# ADS5553.net
KiCad netlist of a schematic drawn in Altium Designer
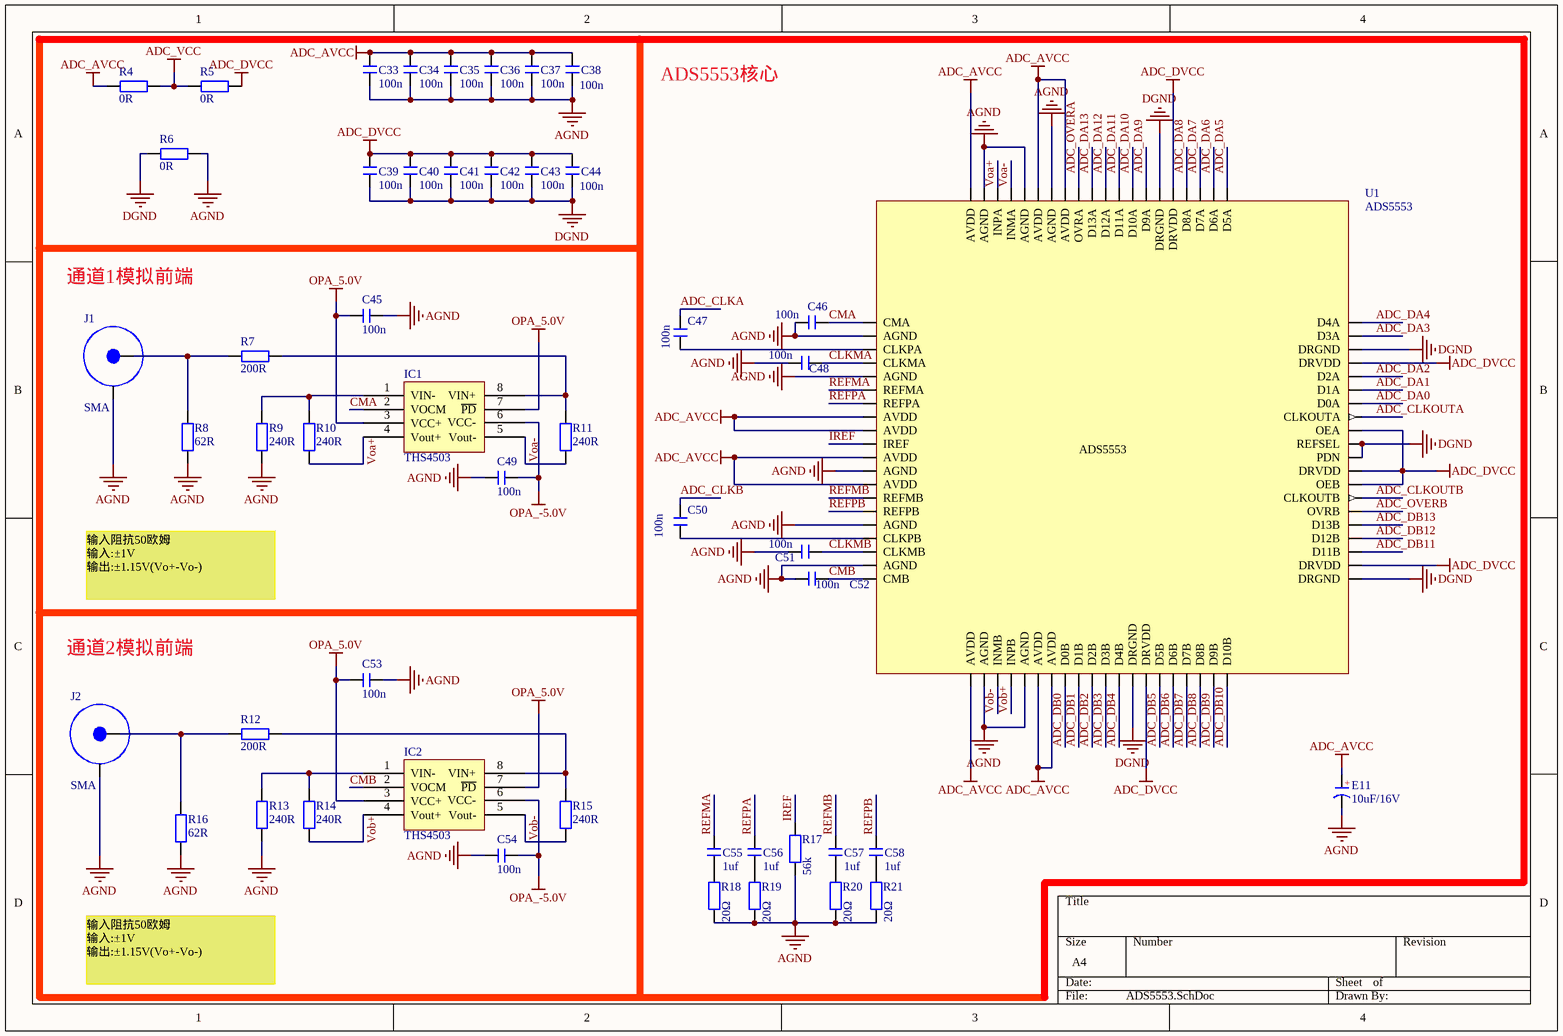
[diagram p0: ADS5553.SchDoc]

(export (version "E")
  (design (tool "Eeschema 10.0.6"))
  (components
    (comp (ref "C33")
      (value "100n")
      (footprint "C 0805_M")
      (description "无极性贴片电容")
      (fields (field (name "版权归属") "源创客"))
      (libsource (lib "3.1   - 电阻-电容-电感") (part "C"))
    )
    (comp (ref "C34")
      (value "100n")
      (footprint "C 0805_M")
      (description "无极性贴片电容")
      (fields (field (name "版权归属") "源创客"))
      (libsource (lib "3.1   - 电阻-电容-电感") (part "C"))
    )
    (comp (ref "C35")
      (value "100n")
      (footprint "C 0805_M")
      (description "无极性贴片电容")
      (fields (field (name "版权归属") "源创客"))
      (libsource (lib "3.1   - 电阻-电容-电感") (part "C"))
    )
    (comp (ref "C36")
      (value "100n")
      (footprint "C 0805_M")
      (description "无极性贴片电容")
      (fields (field (name "版权归属") "源创客"))
      (libsource (lib "3.1   - 电阻-电容-电感") (part "C"))
    )
    (comp (ref "C37")
      (value "100n")
      (footprint "C 0805_M")
      (description "无极性贴片电容")
      (fields (field (name "版权归属") "源创客"))
      (libsource (lib "3.1   - 电阻-电容-电感") (part "C"))
    )
    (comp (ref "C38")
      (value "100n")
      (footprint "C 0805_M")
      (description "无极性贴片电容")
      (fields (field (name "版权归属") "源创客"))
      (libsource (lib "3.1   - 电阻-电容-电感") (part "C"))
    )
    (comp (ref "C39")
      (value "100n")
      (footprint "C 0805_M")
      (description "无极性贴片电容")
      (fields (field (name "版权归属") "源创客"))
      (libsource (lib "3.1   - 电阻-电容-电感") (part "C"))
    )
    (comp (ref "C40")
      (value "100n")
      (footprint "C 0805_M")
      (description "无极性贴片电容")
      (fields (field (name "版权归属") "源创客"))
      (libsource (lib "3.1   - 电阻-电容-电感") (part "C"))
    )
    (comp (ref "C41")
      (value "100n")
      (footprint "C 0805_M")
      (description "无极性贴片电容")
      (fields (field (name "版权归属") "源创客"))
      (libsource (lib "3.1   - 电阻-电容-电感") (part "C"))
    )
    (comp (ref "C42")
      (value "100n")
      (footprint "C 0805_M")
      (description "无极性贴片电容")
      (fields (field (name "版权归属") "源创客"))
      (libsource (lib "3.1   - 电阻-电容-电感") (part "C"))
    )
    (comp (ref "C43")
      (value "100n")
      (footprint "C 0805_M")
      (description "无极性贴片电容")
      (fields (field (name "版权归属") "源创客"))
      (libsource (lib "3.1   - 电阻-电容-电感") (part "C"))
    )
    (comp (ref "C44")
      (value "100n")
      (footprint "C 0805_M")
      (description "无极性贴片电容")
      (fields (field (name "版权归属") "源创客"))
      (libsource (lib "3.1   - 电阻-电容-电感") (part "C"))
    )
    (comp (ref "C45")
      (value "100n")
      (footprint "C 0805_M")
      (description "无极性贴片电容")
      (fields (field (name "版权归属") "源创客"))
      (libsource (lib "3.1   - 电阻-电容-电感") (part "C"))
    )
    (comp (ref "C46")
      (value "100n")
      (footprint "C 0805_M")
      (description "无极性贴片电容")
      (fields (field (name "版权归属") "源创客"))
      (libsource (lib "3.1   - 电阻-电容-电感") (part "C"))
    )
    (comp (ref "C47")
      (value "100n")
      (footprint "C 0805_M")
      (description "无极性贴片电容")
      (fields (field (name "版权归属") "源创客"))
      (libsource (lib "3.1   - 电阻-电容-电感") (part "C"))
    )
    (comp (ref "C48")
      (value "100n")
      (footprint "C 0805_M")
      (description "无极性贴片电容")
      (fields (field (name "版权归属") "源创客"))
      (libsource (lib "3.1   - 电阻-电容-电感") (part "C"))
    )
    (comp (ref "C49")
      (value "100n")
      (footprint "C 0805_M")
      (description "无极性贴片电容")
      (fields (field (name "版权归属") "源创客"))
      (libsource (lib "3.1   - 电阻-电容-电感") (part "C"))
    )
    (comp (ref "C50")
      (value "100n")
      (footprint "C 0805_M")
      (description "无极性贴片电容")
      (fields (field (name "版权归属") "源创客"))
      (libsource (lib "3.1   - 电阻-电容-电感") (part "C"))
    )
    (comp (ref "C51")
      (value "100n")
      (footprint "C 0805_M")
      (description "无极性贴片电容")
      (fields (field (name "版权归属") "源创客"))
      (libsource (lib "3.1   - 电阻-电容-电感") (part "C"))
    )
    (comp (ref "C52")
      (value "100n")
      (footprint "C 0805_M")
      (description "无极性贴片电容")
      (fields (field (name "版权归属") "源创客"))
      (libsource (lib "3.1   - 电阻-电容-电感") (part "C"))
    )
    (comp (ref "C53")
      (value "100n")
      (footprint "C 0805_M")
      (description "无极性贴片电容")
      (fields (field (name "版权归属") "源创客"))
      (libsource (lib "3.1   - 电阻-电容-电感") (part "C"))
    )
    (comp (ref "C54")
      (value "100n")
      (footprint "C 0805_M")
      (description "无极性贴片电容")
      (fields (field (name "版权归属") "源创客"))
      (libsource (lib "3.1   - 电阻-电容-电感") (part "C"))
    )
    (comp (ref "C55")
      (value "1uf")
      (footprint "C 0805_M")
      (description "无极性贴片电容")
      (fields (field (name "版权归属") "源创客"))
      (libsource (lib "3.1   - 电阻-电容-电感") (part "C"))
    )
    (comp (ref "C56")
      (value "1uf")
      (footprint "C 0805_M")
      (description "无极性贴片电容")
      (fields (field (name "版权归属") "源创客"))
      (libsource (lib "3.1   - 电阻-电容-电感") (part "C"))
    )
    (comp (ref "C57")
      (value "1uf")
      (footprint "C 0805_M")
      (description "无极性贴片电容")
      (fields (field (name "版权归属") "源创客"))
      (libsource (lib "3.1   - 电阻-电容-电感") (part "C"))
    )
    (comp (ref "C58")
      (value "1uf")
      (footprint "C 0805_M")
      (description "无极性贴片电容")
      (fields (field (name "版权归属") "源创客"))
      (libsource (lib "3.1   - 电阻-电容-电感") (part "C"))
    )
    (comp (ref "E11")
      (value "10uF/16V")
      (footprint "C 1210_M")
      (description "直插电解电容")
      (fields (field (name "版权归属") "源创客"))
      (libsource (lib "3.1   - 电阻-电容-电感") (part "C-CAP"))
    )
    (comp (ref "IC1")
      (value "THS4503")
      (footprint "SOP8_M")
      (description "外置EEPROM")
      (fields (field (name "版权归属") "源创客"))
      (libsource (lib "1.1   - IC芯片") (part "24Cxx"))
    )
    (comp (ref "IC2")
      (value "THS4503")
      (footprint "SOP8_M")
      (description "外置EEPROM")
      (fields (field (name "版权归属") "源创客"))
      (libsource (lib "1.1   - IC芯片") (part "24Cxx"))
    )
    (comp (ref "J1") (value "SMA") (footprint "SMA_FR") (libsource (lib "RF") (part "SMA")))
    (comp (ref "J2") (value "SMA") (footprint "SMA_FR") (libsource (lib "RF") (part "SMA")))
    (comp (ref "R4")
      (value "0R")
      (footprint "R 0805_M")
      (description "贴片电阻")
      (fields (field (name "版权归属") "源创客"))
      (libsource (lib "3.1   - 电阻-电容-电感") (part "R"))
    )
    (comp (ref "R5")
      (value "0R")
      (footprint "R 0805_M")
      (description "贴片电阻")
      (fields (field (name "版权归属") "源创客"))
      (libsource (lib "3.1   - 电阻-电容-电感") (part "R"))
    )
    (comp (ref "R6")
      (value "0R")
      (footprint "R 1206_M")
      (description "贴片电阻")
      (fields (field (name "版权归属") "源创客"))
      (libsource (lib "3.1   - 电阻-电容-电感") (part "R"))
    )
    (comp (ref "R7")
      (value "200R")
      (footprint "R 0805_M")
      (description "贴片电阻")
      (fields (field (name "版权归属") "源创客"))
      (libsource (lib "3.1   - 电阻-电容-电感") (part "R"))
    )
    (comp (ref "R8")
      (value "62R")
      (footprint "R 0805_M")
      (description "贴片电阻")
      (fields (field (name "版权归属") "源创客"))
      (libsource (lib "3.1   - 电阻-电容-电感") (part "R"))
    )
    (comp (ref "R9")
      (value "240R")
      (footprint "R 0805_M")
      (description "贴片电阻")
      (fields (field (name "版权归属") "源创客"))
      (libsource (lib "3.1   - 电阻-电容-电感") (part "R"))
    )
    (comp (ref "R10")
      (value "240R")
      (footprint "R 0805_M")
      (description "贴片电阻")
      (fields (field (name "版权归属") "源创客"))
      (libsource (lib "3.1   - 电阻-电容-电感") (part "R"))
    )
    (comp (ref "R11")
      (value "240R")
      (footprint "R 0805_M")
      (description "贴片电阻")
      (fields (field (name "版权归属") "源创客"))
      (libsource (lib "3.1   - 电阻-电容-电感") (part "R"))
    )
    (comp (ref "R12")
      (value "200R")
      (footprint "R 0805_M")
      (description "贴片电阻")
      (fields (field (name "版权归属") "源创客"))
      (libsource (lib "3.1   - 电阻-电容-电感") (part "R"))
    )
    (comp (ref "R13")
      (value "240R")
      (footprint "R 0805_M")
      (description "贴片电阻")
      (fields (field (name "版权归属") "源创客"))
      (libsource (lib "3.1   - 电阻-电容-电感") (part "R"))
    )
    (comp (ref "R14")
      (value "240R")
      (footprint "R 0805_M")
      (description "贴片电阻")
      (fields (field (name "版权归属") "源创客"))
      (libsource (lib "3.1   - 电阻-电容-电感") (part "R"))
    )
    (comp (ref "R15")
      (value "240R")
      (footprint "R 0805_M")
      (description "贴片电阻")
      (fields (field (name "版权归属") "源创客"))
      (libsource (lib "3.1   - 电阻-电容-电感") (part "R"))
    )
    (comp (ref "R16")
      (value "62R")
      (footprint "R 0805_M")
      (description "贴片电阻")
      (fields (field (name "版权归属") "源创客"))
      (libsource (lib "3.1   - 电阻-电容-电感") (part "R"))
    )
    (comp (ref "R17")
      (value "56k")
      (footprint "R 0805_M")
      (description "贴片电阻")
      (fields (field (name "版权归属") "源创客"))
      (libsource (lib "3.1   - 电阻-电容-电感") (part "R"))
    )
    (comp (ref "R18")
      (value "20Ω")
      (footprint "R 0805_M")
      (description "贴片电阻")
      (fields (field (name "版权归属") "源创客"))
      (libsource (lib "3.1   - 电阻-电容-电感") (part "R"))
    )
    (comp (ref "R19")
      (value "20Ω")
      (footprint "R 0805_M")
      (description "贴片电阻")
      (fields (field (name "版权归属") "源创客"))
      (libsource (lib "3.1   - 电阻-电容-电感") (part "R"))
    )
    (comp (ref "R20")
      (value "20Ω")
      (footprint "R 0805_M")
      (description "贴片电阻")
      (fields (field (name "版权归属") "源创客"))
      (libsource (lib "3.1   - 电阻-电容-电感") (part "R"))
    )
    (comp (ref "R21")
      (value "20Ω")
      (footprint "R 0805_M")
      (description "贴片电阻")
      (fields (field (name "版权归属") "源创客"))
      (libsource (lib "3.1   - 电阻-电容-电感") (part "R"))
    )
    (comp (ref "U1")
      (value "ADS5553")
      (footprint "LQFP80 12x12_M")
      (libsource (lib "ADS5553") (part "ADS5553"))
    )
  )
  (nets
    (net (code "1") (name "/ADC_CLKA") (class "Default")
      (node (ref "C47") (pin "2") (pinfunction "2_2") (pintype "passive"))
    )
    (net (code "2") (name "/ADC_CLKB") (class "Default")
      (node (ref "C50") (pin "2") (pinfunction "2_2") (pintype "passive"))
    )
    (net (code "3") (name "/ADC_CLKOUTA") (class "Default")
      (node (ref "U1") (pin "53") (pinfunction "CLKOUTA_53") (pintype "output"))
    )
    (net (code "4") (name "/ADC_CLKOUTB") (class "Default")
      (node (ref "U1") (pin "47") (pinfunction "CLKOUTB_47") (pintype "output"))
    )
    (net (code "5") (name "/ADC_DA0") (class "Default")
      (node (ref "U1") (pin "54") (pinfunction "D0A_54") (pintype "passive"))
    )
    (net (code "6") (name "/ADC_DA1") (class "Default")
      (node (ref "U1") (pin "55") (pinfunction "D1A_55") (pintype "passive"))
    )
    (net (code "7") (name "/ADC_DA2") (class "Default")
      (node (ref "U1") (pin "56") (pinfunction "D2A_56") (pintype "passive"))
    )
    (net (code "8") (name "/ADC_DA3") (class "Default")
      (node (ref "U1") (pin "59") (pinfunction "D3A_59") (pintype "passive"))
    )
    (net (code "9") (name "/ADC_DA4") (class "Default")
      (node (ref "U1") (pin "60") (pinfunction "D4A_60") (pintype "passive"))
    )
    (net (code "10") (name "/ADC_DA5") (class "Default")
      (node (ref "U1") (pin "61") (pinfunction "D5A_61") (pintype "passive"))
    )
    (net (code "11") (name "/ADC_DA6") (class "Default")
      (node (ref "U1") (pin "62") (pinfunction "D6A_62") (pintype "passive"))
    )
    (net (code "12") (name "/ADC_DA7") (class "Default")
      (node (ref "U1") (pin "63") (pinfunction "D7A_63") (pintype "passive"))
    )
    (net (code "13") (name "/ADC_DA8") (class "Default")
      (node (ref "U1") (pin "64") (pinfunction "D8A_64") (pintype "passive"))
    )
    (net (code "14") (name "/ADC_DA9") (class "Default")
      (node (ref "U1") (pin "67") (pinfunction "D9A_67") (pintype "passive"))
    )
    (net (code "15") (name "/ADC_DA10") (class "Default")
      (node (ref "U1") (pin "68") (pinfunction "D10A_68") (pintype "passive"))
    )
    (net (code "16") (name "/ADC_DA11") (class "Default")
      (node (ref "U1") (pin "69") (pinfunction "D11A_69") (pintype "passive"))
    )
    (net (code "17") (name "/ADC_DA12") (class "Default")
      (node (ref "U1") (pin "70") (pinfunction "D12A_70") (pintype "passive"))
    )
    (net (code "18") (name "/ADC_DA13") (class "Default")
      (node (ref "U1") (pin "71") (pinfunction "D13A_71") (pintype "passive"))
    )
    (net (code "19") (name "/ADC_DB0") (class "Default")
      (node (ref "U1") (pin "28") (pinfunction "D0B_28") (pintype "passive"))
    )
    (net (code "20") (name "/ADC_DB1") (class "Default")
      (node (ref "U1") (pin "29") (pinfunction "D1B_29") (pintype "passive"))
    )
    (net (code "21") (name "/ADC_DB2") (class "Default")
      (node (ref "U1") (pin "30") (pinfunction "D2B_30") (pintype "passive"))
    )
    (net (code "22") (name "/ADC_DB3") (class "Default")
      (node (ref "U1") (pin "31") (pinfunction "D3B_31") (pintype "passive"))
    )
    (net (code "23") (name "/ADC_DB4") (class "Default")
      (node (ref "U1") (pin "32") (pinfunction "D4B_32") (pintype "passive"))
    )
    (net (code "24") (name "/ADC_DB5") (class "Default")
      (node (ref "U1") (pin "35") (pinfunction "D5B_35") (pintype "passive"))
    )
    (net (code "25") (name "/ADC_DB6") (class "Default")
      (node (ref "U1") (pin "36") (pinfunction "D6B_36") (pintype "passive"))
    )
    (net (code "26") (name "/ADC_DB7") (class "Default")
      (node (ref "U1") (pin "37") (pinfunction "D7B_37") (pintype "passive"))
    )
    (net (code "27") (name "/ADC_DB8") (class "Default")
      (node (ref "U1") (pin "38") (pinfunction "D8B_38") (pintype "passive"))
    )
    (net (code "28") (name "/ADC_DB9") (class "Default")
      (node (ref "U1") (pin "39") (pinfunction "D9B_39") (pintype "passive"))
    )
    (net (code "29") (name "/ADC_DB10") (class "Default")
      (node (ref "U1") (pin "40") (pinfunction "D10B_40") (pintype "passive"))
    )
    (net (code "30") (name "/ADC_DB11") (class "Default")
      (node (ref "U1") (pin "43") (pinfunction "D11B_43") (pintype "passive"))
    )
    (net (code "31") (name "/ADC_DB12") (class "Default")
      (node (ref "U1") (pin "44") (pinfunction "D12B_44") (pintype "passive"))
    )
    (net (code "32") (name "/ADC_DB13") (class "Default")
      (node (ref "U1") (pin "45") (pinfunction "D13B_45") (pintype "passive"))
    )
    (net (code "33") (name "/ADC_OVERA") (class "Default")
      (node (ref "U1") (pin "72") (pinfunction "OVRA_72") (pintype "passive"))
    )
    (net (code "34") (name "/ADC_OVERB") (class "Default")
      (node (ref "U1") (pin "46") (pinfunction "OVRB_46") (pintype "passive"))
    )
    (net (code "35") (name "/CLKMA") (class "Default")
      (node (ref "C48") (pin "2") (pinfunction "2_2") (pintype "passive"))
      (node (ref "U1") (pin "4") (pinfunction "CLKMA_4") (pintype "passive"))
    )
    (net (code "36") (name "/CLKMB") (class "Default")
      (node (ref "C51") (pin "2") (pinfunction "2_2") (pintype "passive"))
      (node (ref "U1") (pin "18") (pinfunction "CLKMB_18") (pintype "passive"))
    )
    (net (code "37") (name "/CMA") (class "Default")
      (node (ref "C46") (pin "2") (pinfunction "2_2") (pintype "passive"))
      (node (ref "IC1") (pin "2") (pinfunction "VOCM_2") (pintype "passive"))
      (node (ref "U1") (pin "1") (pinfunction "CMA_1") (pintype "passive"))
    )
    (net (code "38") (name "/CMB") (class "Default")
      (node (ref "C52") (pin "2") (pinfunction "2_2") (pintype "passive"))
      (node (ref "IC2") (pin "2") (pinfunction "VOCM_2") (pintype "passive"))
      (node (ref "U1") (pin "20") (pinfunction "CMB_20") (pintype "passive"))
    )
    (net (code "39") (name "/IREF") (class "Default")
      (node (ref "R17") (pin "2") (pinfunction "2_2") (pintype "passive"))
      (node (ref "U1") (pin "10") (pinfunction "IREF_10") (pintype "passive"))
    )
    (net (code "40") (name "/REFMA") (class "Default")
      (node (ref "C55") (pin "2") (pinfunction "2_2") (pintype "passive"))
      (node (ref "U1") (pin "6") (pinfunction "REFMA_6") (pintype "passive"))
    )
    (net (code "41") (name "/REFMB") (class "Default")
      (node (ref "C57") (pin "2") (pinfunction "2_2") (pintype "passive"))
      (node (ref "U1") (pin "14") (pinfunction "REFMB_14") (pintype "passive"))
    )
    (net (code "42") (name "/REFPA") (class "Default")
      (node (ref "C56") (pin "2") (pinfunction "2_2") (pintype "passive"))
      (node (ref "U1") (pin "7") (pinfunction "REFPA_7") (pintype "passive"))
    )
    (net (code "43") (name "/REFPB") (class "Default")
      (node (ref "C58") (pin "2") (pinfunction "2_2") (pintype "passive"))
      (node (ref "U1") (pin "15") (pinfunction "REFPB_15") (pintype "passive"))
    )
    (net (code "44") (name "/Voa+") (class "Default")
      (node (ref "IC1") (pin "4") (pinfunction "Vout+_4") (pintype "passive"))
      (node (ref "R10") (pin "1") (pinfunction "1_1") (pintype "passive"))
      (node (ref "U1") (pin "78") (pinfunction "INPA_78") (pintype "passive"))
    )
    (net (code "45") (name "/Voa-") (class "Default")
      (node (ref "IC1") (pin "5") (pinfunction "Vout-_5") (pintype "passive"))
      (node (ref "R11") (pin "1") (pinfunction "1_1") (pintype "passive"))
      (node (ref "U1") (pin "77") (pinfunction "INMA_77") (pintype "passive"))
    )
    (net (code "46") (name "/Vob+") (class "Default")
      (node (ref "IC2") (pin "4") (pinfunction "Vout+_4") (pintype "passive"))
      (node (ref "R14") (pin "1") (pinfunction "1_1") (pintype "passive"))
      (node (ref "U1") (pin "24") (pinfunction "INPB_24") (pintype "passive"))
    )
    (net (code "47") (name "/Vob-") (class "Default")
      (node (ref "IC2") (pin "5") (pinfunction "Vout-_5") (pintype "passive"))
      (node (ref "R15") (pin "1") (pinfunction "1_1") (pintype "passive"))
      (node (ref "U1") (pin "23") (pinfunction "INMB_23") (pintype "passive"))
    )
    (net (code "48") (name "ADC_AVCC") (class "Default")
      (node (ref "C33") (pin "2") (pinfunction "2_2") (pintype "passive"))
      (node (ref "C34") (pin "2") (pinfunction "2_2") (pintype "passive"))
      (node (ref "C35") (pin "2") (pinfunction "2_2") (pintype "passive"))
      (node (ref "C36") (pin "2") (pinfunction "2_2") (pintype "passive"))
      (node (ref "C37") (pin "2") (pinfunction "2_2") (pintype "passive"))
      (node (ref "C38") (pin "2") (pinfunction "2_2") (pintype "passive"))
      (node (ref "E11") (pin "1") (pinfunction "A_1") (pintype "passive"))
      (node (ref "R4") (pin "2") (pinfunction "2_2") (pintype "passive"))
      (node (ref "U1") (pin "11") (pinfunction "AVDD_11") (pintype "passive"))
      (node (ref "U1") (pin "13") (pinfunction "AVDD_13") (pintype "passive"))
      (node (ref "U1") (pin "21") (pinfunction "AVDD_21") (pintype "passive"))
      (node (ref "U1") (pin "26") (pinfunction "AVDD_26") (pintype "passive"))
      (node (ref "U1") (pin "27") (pinfunction "AVDD_27") (pintype "passive"))
      (node (ref "U1") (pin "73") (pinfunction "AVDD_73") (pintype "passive"))
      (node (ref "U1") (pin "75") (pinfunction "AVDD_75") (pintype "passive"))
      (node (ref "U1") (pin "8") (pinfunction "AVDD_8") (pintype "passive"))
      (node (ref "U1") (pin "80") (pinfunction "AVDD_80") (pintype "passive"))
      (node (ref "U1") (pin "9") (pinfunction "AVDD_9") (pintype "passive"))
    )
    (net (code "49") (name "ADC_DVCC") (class "Default")
      (node (ref "C39") (pin "2") (pinfunction "2_2") (pintype "passive"))
      (node (ref "C40") (pin "2") (pinfunction "2_2") (pintype "passive"))
      (node (ref "C41") (pin "2") (pinfunction "2_2") (pintype "passive"))
      (node (ref "C42") (pin "2") (pinfunction "2_2") (pintype "passive"))
      (node (ref "C43") (pin "2") (pinfunction "2_2") (pintype "passive"))
      (node (ref "C44") (pin "2") (pinfunction "2_2") (pintype "passive"))
      (node (ref "R5") (pin "1") (pinfunction "1_1") (pintype "passive"))
      (node (ref "U1") (pin "34") (pinfunction "DRVDD_34") (pintype "passive"))
      (node (ref "U1") (pin "42") (pinfunction "DRVDD_42") (pintype "passive"))
      (node (ref "U1") (pin "48") (pinfunction "OEB_48") (pintype "passive"))
      (node (ref "U1") (pin "49") (pinfunction "DRVDD_49") (pintype "passive"))
      (node (ref "U1") (pin "52") (pinfunction "OEA_52") (pintype "passive"))
      (node (ref "U1") (pin "57") (pinfunction "DRVDD_57") (pintype "passive"))
      (node (ref "U1") (pin "65") (pinfunction "DRVDD_65") (pintype "passive"))
    )
    (net (code "50") (name "ADC_VCC") (class "Default")
      (node (ref "R4") (pin "1") (pinfunction "1_1") (pintype "passive"))
      (node (ref "R5") (pin "2") (pinfunction "2_2") (pintype "passive"))
    )
    (net (code "51") (name "AGND") (class "Default")
      (node (ref "C33") (pin "1") (pinfunction "1_1") (pintype "passive"))
      (node (ref "C34") (pin "1") (pinfunction "1_1") (pintype "passive"))
      (node (ref "C35") (pin "1") (pinfunction "1_1") (pintype "passive"))
      (node (ref "C36") (pin "1") (pinfunction "1_1") (pintype "passive"))
      (node (ref "C37") (pin "1") (pinfunction "1_1") (pintype "passive"))
      (node (ref "C38") (pin "1") (pinfunction "1_1") (pintype "passive"))
      (node (ref "C45") (pin "2") (pinfunction "2_2") (pintype "passive"))
      (node (ref "C46") (pin "1") (pinfunction "1_1") (pintype "passive"))
      (node (ref "C48") (pin "1") (pinfunction "1_1") (pintype "passive"))
      (node (ref "C49") (pin "1") (pinfunction "1_1") (pintype "passive"))
      (node (ref "C51") (pin "1") (pinfunction "1_1") (pintype "passive"))
      (node (ref "C52") (pin "1") (pinfunction "1_1") (pintype "passive"))
      (node (ref "C53") (pin "2") (pinfunction "2_2") (pintype "passive"))
      (node (ref "C54") (pin "1") (pinfunction "1_1") (pintype "passive"))
      (node (ref "E11") (pin "2") (pinfunction "K_2") (pintype "passive"))
      (node (ref "J1") (pin "2") (pinfunction "2_2") (pintype "passive"))
      (node (ref "J2") (pin "2") (pinfunction "2_2") (pintype "passive"))
      (node (ref "R13") (pin "1") (pinfunction "1_1") (pintype "passive"))
      (node (ref "R16") (pin "1") (pinfunction "1_1") (pintype "passive"))
      (node (ref "R17") (pin "1") (pinfunction "1_1") (pintype "passive"))
      (node (ref "R18") (pin "1") (pinfunction "1_1") (pintype "passive"))
      (node (ref "R19") (pin "1") (pinfunction "1_1") (pintype "passive"))
      (node (ref "R20") (pin "1") (pinfunction "1_1") (pintype "passive"))
      (node (ref "R21") (pin "1") (pinfunction "1_1") (pintype "passive"))
      (node (ref "R6") (pin "1") (pinfunction "1_1") (pintype "passive"))
      (node (ref "R8") (pin "2") (pinfunction "2_2") (pintype "passive"))
      (node (ref "R9") (pin "1") (pinfunction "1_1") (pintype "passive"))
      (node (ref "U1") (pin "12") (pinfunction "AGND_12") (pintype "passive"))
      (node (ref "U1") (pin "16") (pinfunction "AGND_16") (pintype "passive"))
      (node (ref "U1") (pin "19") (pinfunction "AGND_19") (pintype "passive"))
      (node (ref "U1") (pin "2") (pinfunction "AGND_2") (pintype "passive"))
      (node (ref "U1") (pin "22") (pinfunction "AGND_22") (pintype "passive"))
      (node (ref "U1") (pin "25") (pinfunction "AGND_25") (pintype "passive"))
      (node (ref "U1") (pin "5") (pinfunction "AGND_5") (pintype "passive"))
      (node (ref "U1") (pin "74") (pinfunction "AGND_74") (pintype "passive"))
      (node (ref "U1") (pin "76") (pinfunction "AGND_76") (pintype "passive"))
      (node (ref "U1") (pin "79") (pinfunction "AGND_79") (pintype "passive"))
    )
    (net (code "52") (name "DGND") (class "Default")
      (node (ref "C39") (pin "1") (pinfunction "1_1") (pintype "passive"))
      (node (ref "C40") (pin "1") (pinfunction "1_1") (pintype "passive"))
      (node (ref "C41") (pin "1") (pinfunction "1_1") (pintype "passive"))
      (node (ref "C42") (pin "1") (pinfunction "1_1") (pintype "passive"))
      (node (ref "C43") (pin "1") (pinfunction "1_1") (pintype "passive"))
      (node (ref "C44") (pin "1") (pinfunction "1_1") (pintype "passive"))
      (node (ref "R6") (pin "2") (pinfunction "2_2") (pintype "passive"))
      (node (ref "U1") (pin "33") (pinfunction "DRGND_33") (pintype "passive"))
      (node (ref "U1") (pin "41") (pinfunction "DRGND_41") (pintype "passive"))
      (node (ref "U1") (pin "50") (pinfunction "PDN_50") (pintype "passive"))
      (node (ref "U1") (pin "51") (pinfunction "REFSEL_51") (pintype "passive"))
      (node (ref "U1") (pin "58") (pinfunction "DRGND_58") (pintype "passive"))
      (node (ref "U1") (pin "66") (pinfunction "DRGND_66") (pintype "passive"))
    )
    (net (code "53") (name "Net-(C55-Pad1)") (class "Default")
      (node (ref "C55") (pin "1") (pinfunction "1_1") (pintype "passive"))
      (node (ref "R18") (pin "2") (pinfunction "2_2") (pintype "passive"))
    )
    (net (code "54") (name "Net-(C56-Pad1)") (class "Default")
      (node (ref "C56") (pin "1") (pinfunction "1_1") (pintype "passive"))
      (node (ref "R19") (pin "2") (pinfunction "2_2") (pintype "passive"))
    )
    (net (code "55") (name "Net-(C57-Pad1)") (class "Default")
      (node (ref "C57") (pin "1") (pinfunction "1_1") (pintype "passive"))
      (node (ref "R20") (pin "2") (pinfunction "2_2") (pintype "passive"))
    )
    (net (code "56") (name "Net-(C58-Pad1)") (class "Default")
      (node (ref "C58") (pin "1") (pinfunction "1_1") (pintype "passive"))
      (node (ref "R21") (pin "2") (pinfunction "2_2") (pintype "passive"))
    )
    (net (code "57") (name "Net-(IC1-VIN+)") (class "Default")
      (node (ref "IC1") (pin "8") (pinfunction "VIN+_8") (pintype "passive"))
      (node (ref "R11") (pin "2") (pinfunction "2_2") (pintype "passive"))
      (node (ref "R7") (pin "1") (pinfunction "1_1") (pintype "passive"))
    )
    (net (code "58") (name "Net-(IC1-VIN-)") (class "Default")
      (node (ref "IC1") (pin "1") (pinfunction "VIN-_1") (pintype "passive"))
      (node (ref "R10") (pin "2") (pinfunction "2_2") (pintype "passive"))
      (node (ref "R9") (pin "2") (pinfunction "2_2") (pintype "passive"))
    )
    (net (code "59") (name "Net-(IC2-VIN+)") (class "Default")
      (node (ref "IC2") (pin "8") (pinfunction "VIN+_8") (pintype "passive"))
      (node (ref "R12") (pin "1") (pinfunction "1_1") (pintype "passive"))
      (node (ref "R15") (pin "2") (pinfunction "2_2") (pintype "passive"))
    )
    (net (code "60") (name "Net-(IC2-VIN-)") (class "Default")
      (node (ref "IC2") (pin "1") (pinfunction "VIN-_1") (pintype "passive"))
      (node (ref "R13") (pin "2") (pinfunction "2_2") (pintype "passive"))
      (node (ref "R14") (pin "2") (pinfunction "2_2") (pintype "passive"))
    )
    (net (code "61") (name "Net-(J1-Pad1)") (class "Default")
      (node (ref "J1") (pin "1") (pinfunction "1_1") (pintype "passive"))
      (node (ref "R7") (pin "2") (pinfunction "2_2") (pintype "passive"))
      (node (ref "R8") (pin "1") (pinfunction "1_1") (pintype "passive"))
    )
    (net (code "62") (name "Net-(J2-Pad1)") (class "Default")
      (node (ref "J2") (pin "1") (pinfunction "1_1") (pintype "passive"))
      (node (ref "R12") (pin "2") (pinfunction "2_2") (pintype "passive"))
      (node (ref "R16") (pin "2") (pinfunction "2_2") (pintype "passive"))
    )
    (net (code "63") (name "Net-(U1-CLKPA)") (class "Default")
      (node (ref "C47") (pin "1") (pinfunction "1_1") (pintype "passive"))
      (node (ref "U1") (pin "3") (pinfunction "CLKPA_3") (pintype "passive"))
    )
    (net (code "64") (name "Net-(U1-CLKPB)") (class "Default")
      (node (ref "C50") (pin "1") (pinfunction "1_1") (pintype "passive"))
      (node (ref "U1") (pin "17") (pinfunction "CLKPB_17") (pintype "passive"))
    )
    (net (code "65") (name "OPA_-5.0V") (class "Default")
      (node (ref "C49") (pin "2") (pinfunction "2_2") (pintype "passive"))
      (node (ref "C54") (pin "2") (pinfunction "2_2") (pintype "passive"))
      (node (ref "IC1") (pin "6") (pinfunction "VCC-_6") (pintype "passive"))
      (node (ref "IC2") (pin "6") (pinfunction "VCC-_6") (pintype "passive"))
    )
    (net (code "66") (name "OPA_5.0V") (class "Default")
      (node (ref "C45") (pin "1") (pinfunction "1_1") (pintype "passive"))
      (node (ref "C53") (pin "1") (pinfunction "1_1") (pintype "passive"))
      (node (ref "IC1") (pin "3") (pinfunction "VCC+_3") (pintype "passive"))
      (node (ref "IC1") (pin "7") (pinfunction "~{PD}_7") (pintype "passive"))
      (node (ref "IC2") (pin "3") (pinfunction "VCC+_3") (pintype "passive"))
      (node (ref "IC2") (pin "7") (pinfunction "~{PD}_7") (pintype "passive"))
    )
  )
)
